# SHDN-BSPD-S01-V00-BSPDBoard.net
KiCad netlist of a schematic drawn in Altium Designer
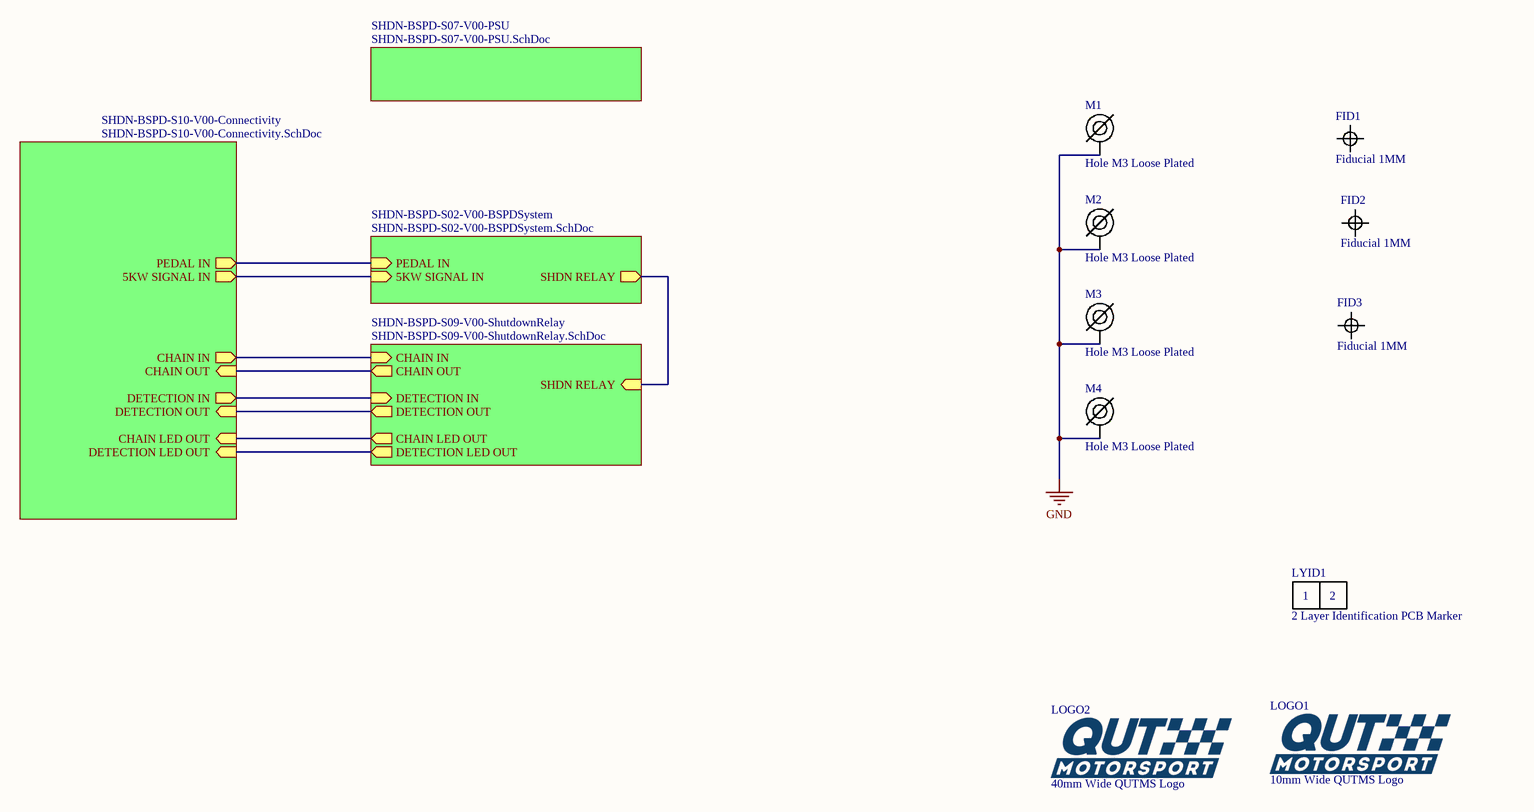
[diagram p0: SHDN-BSPD-S01-V00-BSPDBoard.SchDoc]

(export (version "E")
  (design (tool "Eeschema 10.0.6"))
  (components
    (comp (ref "FID1")
      (value "Fiducial 1MM")
      (footprint "FIDUCIAL 1MM")
      (libsource (lib "QUTMS_PCBLibrary") (part "Fiducial 1MM"))
    )
    (comp (ref "FID2")
      (value "Fiducial 1MM")
      (footprint "FIDUCIAL 1MM")
      (libsource (lib "QUTMS_PCBLibrary") (part "Fiducial 1MM"))
    )
    (comp (ref "FID3")
      (value "Fiducial 1MM")
      (footprint "FIDUCIAL 1MM")
      (libsource (lib "QUTMS_PCBLibrary") (part "Fiducial 1MM"))
    )
    (comp (ref "LOGO1")
      (value "10mm Wide QUTMS Logo")
      (footprint "QUTMS LOGO 10MM")
      (libsource (lib "QUTMS_PCBLibrary") (part "QUTMS Logo 10mm"))
    )
    (comp (ref "LOGO2")
      (value "40mm Wide QUTMS Logo")
      (footprint "QUTMS LOGO 40MM")
      (libsource (lib "QUTMS_PCBLibrary") (part "QUTMS Logo 40mm"))
    )
    (comp (ref "LYID1")
      (value "2 Layer Identification PCB Marker")
      (footprint "LAYER IDENT 2")
      (libsource (lib "QUTMS_PCBLibrary") (part "Layer Identification 2"))
    )
    (comp (ref "M1")
      (value "Hole M3 Loose Plated")
      (footprint "M3.5 PLATED")
      (description "M3.5 Hole, Plated")
      (libsource (lib "QUTMS_PCBLibrary") (part "Hole M3 Loose Plated"))
    )
    (comp (ref "M2")
      (value "Hole M3 Loose Plated")
      (footprint "M3.5 PLATED")
      (description "M3.5 Hole, Plated")
      (libsource (lib "QUTMS_PCBLibrary") (part "Hole M3 Loose Plated"))
    )
    (comp (ref "M3")
      (value "Hole M3 Loose Plated")
      (footprint "M3.5 PLATED")
      (description "M3.5 Hole, Plated")
      (libsource (lib "QUTMS_PCBLibrary") (part "Hole M3 Loose Plated"))
    )
    (comp (ref "M4")
      (value "Hole M3 Loose Plated")
      (footprint "M3.5 PLATED")
      (description "M3.5 Hole, Plated")
      (libsource (lib "QUTMS_PCBLibrary") (part "Hole M3 Loose Plated"))
    )
  )
  (nets
    (net (code "10") (name "GND") (class "Default")
      (node (ref "M1") (pin "1") (pinfunction "1_1") (pintype "passive"))
      (node (ref "M2") (pin "1") (pinfunction "1_1") (pintype "passive"))
      (node (ref "M3") (pin "1") (pinfunction "1_1") (pintype "passive"))
      (node (ref "M4") (pin "1") (pinfunction "1_1") (pintype "passive"))
    )
  )
)
